# BackPage.net
KiCad netlist of a schematic drawn in Altium Designer
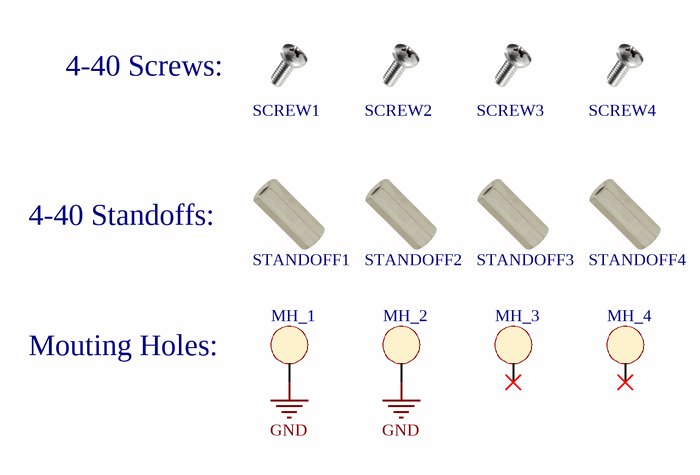
[diagram p0: BackPage.SchDoc]

(export (version "E")
  (design (tool "Eeschema 10.0.6"))
  (components
    (comp (ref "MH_1")
      (value "MOUNTING_HOLE")
      (footprint "MOUNTING_HOLE")
      (libsource (lib "CAN") (part "MOUNTING_HOLE"))
    )
    (comp (ref "MH_2")
      (value "MOUNTING_HOLE")
      (footprint "MOUNTING_HOLE")
      (libsource (lib "CAN") (part "MOUNTING_HOLE"))
    )
    (comp (ref "MH_3")
      (value "MOUNTING_HOLE")
      (footprint "MOUNTING_HOLE")
      (libsource (lib "CAN") (part "MOUNTING_HOLE"))
    )
    (comp (ref "MH_4")
      (value "MOUNTING_HOLE")
      (footprint "MOUNTING_HOLE")
      (libsource (lib "CAN") (part "MOUNTING_HOLE"))
    )
    (comp (ref "SCREW1") (value "Screw-4-40") (libsource (lib "AMDC") (part "Screw-4-40")))
    (comp (ref "SCREW2") (value "Screw-4-40") (libsource (lib "AMDC") (part "Screw-4-40")))
    (comp (ref "SCREW3") (value "Screw-4-40") (libsource (lib "AMDC") (part "Screw-4-40")))
    (comp (ref "SCREW4") (value "Screw-4-40") (libsource (lib "AMDC") (part "Screw-4-40")))
    (comp (ref "STANDOFF1") (value "Standoff-4-40") (libsource (lib "AMDC") (part "Standoff-4-40")))
    (comp (ref "STANDOFF2") (value "Standoff-4-40") (libsource (lib "AMDC") (part "Standoff-4-40")))
    (comp (ref "STANDOFF3") (value "Standoff-4-40") (libsource (lib "AMDC") (part "Standoff-4-40")))
    (comp (ref "STANDOFF4") (value "Standoff-4-40") (libsource (lib "AMDC") (part "Standoff-4-40")))
  )
  (nets
    (net (code "1") (name "GND") (class "Default")
      (node (ref "MH_1") (pin "1") (pinfunction "1_1") (pintype "passive"))
      (node (ref "MH_2") (pin "1") (pinfunction "1_1") (pintype "passive"))
    )
    (net (code "2") (name "unconnected-(MH_3-Pad1)") (class "Default")
      (node (ref "MH_3") (pin "1") (pinfunction "1_1") (pintype "passive+no_connect"))
    )
    (net (code "3") (name "unconnected-(MH_4-Pad1)") (class "Default")
      (node (ref "MH_4") (pin "1") (pinfunction "1_1") (pintype "passive+no_connect"))
    )
  )
)
